# MPU-9250-mbed_rev03_FDZ.net
KiCad netlist of a schematic drawn in EAGLE
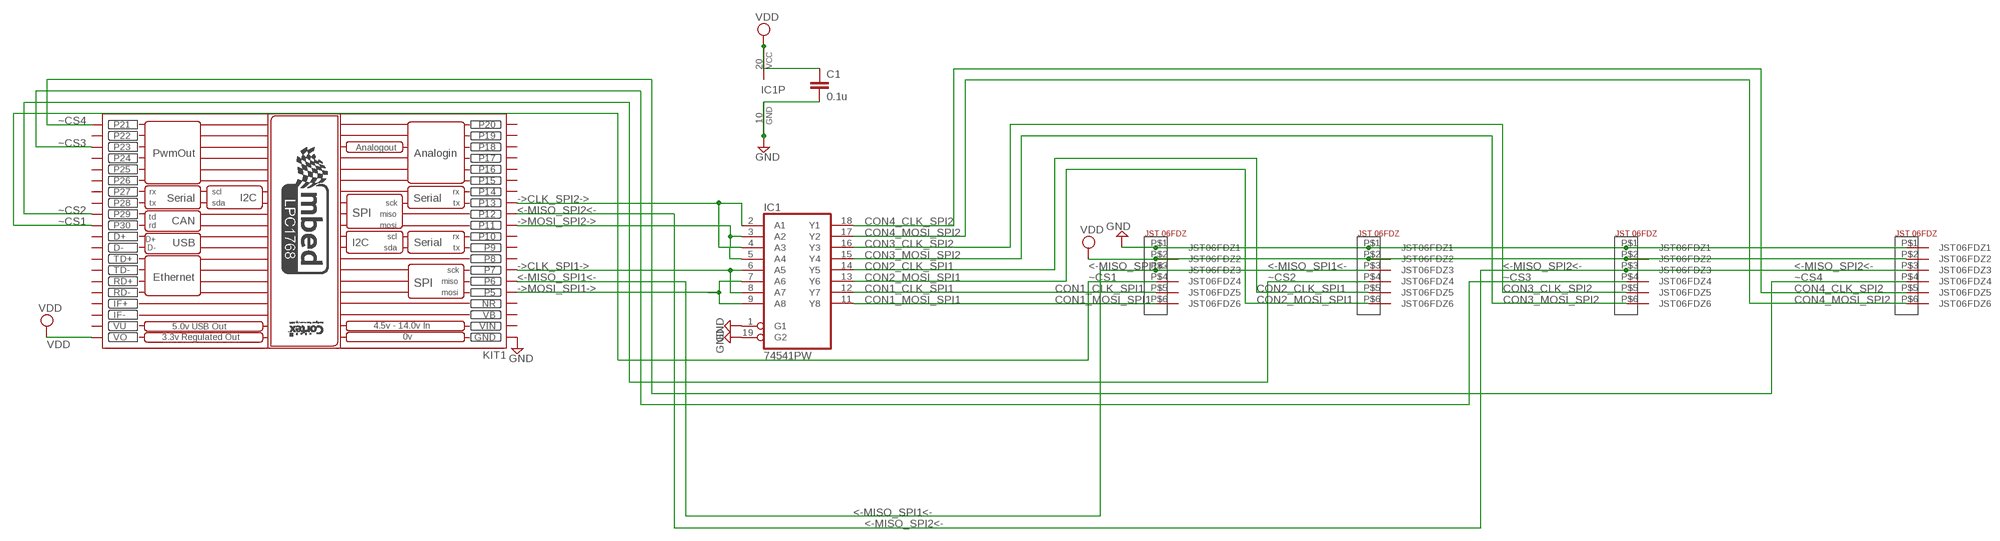
[diagram p0: schematic, sheet 1]

(export (version "E")
  (design (tool "Eeschema 10.0.6"))
  (components
    (comp (ref "C1")
      (value "0.1u")
      (footprint "eagle-import:C5B3")
      (libsource (lib "eagle-import") (part "C5/3"))
    )
    (comp (ref "CH0")
      (value "CH0")
      (footprint "eagle-import:06FDZ-ST(S)")
      (libsource (lib "eagle-import") (part "06FDZ-ST(S)"))
    )
    (comp (ref "IC1")
      (value "74541PW")
      (footprint "eagle-import:TSSOP20")
      (libsource (lib "eagle-import") (part "74541PW"))
    )
    (comp (ref "KIT1")
      (value "MBED_NXP_LPC1768")
      (footprint "eagle-import:MBED-KIT")
      (libsource (lib "eagle-import") (part "MBED_NXP_LPC1768"))
    )
    (comp (ref "U$2")
      (value "06FDZ-ST(S)")
      (footprint "eagle-import:06FDZ-ST(S)")
      (libsource (lib "eagle-import") (part "06FDZ-ST(S)"))
    )
    (comp (ref "U$3")
      (value "06FDZ-ST(S)")
      (footprint "eagle-import:06FDZ-ST(S)")
      (libsource (lib "eagle-import") (part "06FDZ-ST(S)"))
    )
    (comp (ref "U$4")
      (value "06FDZ-ST(S)")
      (footprint "eagle-import:06FDZ-ST(S)")
      (libsource (lib "eagle-import") (part "06FDZ-ST(S)"))
    )
  )
  (nets
    (net (code "1") (name "/->CLK_SPI1->") (class "Default")
      (node (ref "IC1") (pin "6") (pinfunction "A5_6") (pintype "input"))
      (node (ref "IC1") (pin "8") (pinfunction "A7_8") (pintype "input"))
      (node (ref "KIT1") (pin "P$7") (pinfunction "P7_P$7") (pintype "bidirectional"))
    )
    (net (code "2") (name "/->CLK_SPI2->") (class "Default")
      (node (ref "IC1") (pin "2") (pinfunction "A1_2") (pintype "input"))
      (node (ref "IC1") (pin "4") (pinfunction "A3_4") (pintype "input"))
      (node (ref "KIT1") (pin "P$13") (pinfunction "P13_P$13") (pintype "bidirectional"))
    )
    (net (code "3") (name "/->MOSI_SPI1->") (class "Default")
      (node (ref "IC1") (pin "7") (pinfunction "A6_7") (pintype "input"))
      (node (ref "IC1") (pin "9") (pinfunction "A8_9") (pintype "input"))
      (node (ref "KIT1") (pin "P$5") (pinfunction "P5_P$5") (pintype "bidirectional"))
    )
    (net (code "4") (name "/->MOSI_SPI2->") (class "Default")
      (node (ref "IC1") (pin "3") (pinfunction "A2_3") (pintype "input"))
      (node (ref "IC1") (pin "5") (pinfunction "A4_5") (pintype "input"))
      (node (ref "KIT1") (pin "P$11") (pinfunction "P11_P$11") (pintype "bidirectional"))
    )
    (net (code "5") (name "/<-MISO_SPI1<-") (class "Default")
      (node (ref "CH0") (pin "P$3") (pinfunction "JST06FDZ3_P$3") (pintype "bidirectional"))
      (node (ref "KIT1") (pin "P$6") (pinfunction "P6_P$6") (pintype "bidirectional"))
      (node (ref "U$2") (pin "P$3") (pinfunction "JST06FDZ3_P$3") (pintype "bidirectional"))
    )
    (net (code "6") (name "/<-MISO_SPI2<-") (class "Default")
      (node (ref "KIT1") (pin "P$12") (pinfunction "P12_P$12") (pintype "bidirectional"))
      (node (ref "U$3") (pin "P$3") (pinfunction "JST06FDZ3_P$3") (pintype "bidirectional"))
      (node (ref "U$4") (pin "P$3") (pinfunction "JST06FDZ3_P$3") (pintype "bidirectional"))
    )
    (net (code "7") (name "/CON1_CLK_SPI1") (class "Default")
      (node (ref "CH0") (pin "P$5") (pinfunction "JST06FDZ5_P$5") (pintype "bidirectional"))
      (node (ref "IC1") (pin "12") (pinfunction "Y7_12") (pintype "tri_state"))
    )
    (net (code "8") (name "/CON1_MOSI_SPI1") (class "Default")
      (node (ref "CH0") (pin "P$6") (pinfunction "JST06FDZ6_P$6") (pintype "bidirectional"))
      (node (ref "IC1") (pin "11") (pinfunction "Y8_11") (pintype "tri_state"))
    )
    (net (code "9") (name "/CON2_CLK_SPI1") (class "Default")
      (node (ref "IC1") (pin "14") (pinfunction "Y5_14") (pintype "tri_state"))
      (node (ref "U$2") (pin "P$5") (pinfunction "JST06FDZ5_P$5") (pintype "bidirectional"))
    )
    (net (code "10") (name "/CON2_MOSI_SPI1") (class "Default")
      (node (ref "IC1") (pin "13") (pinfunction "Y6_13") (pintype "tri_state"))
      (node (ref "U$2") (pin "P$6") (pinfunction "JST06FDZ6_P$6") (pintype "bidirectional"))
    )
    (net (code "11") (name "/CON3_CLK_SPI2") (class "Default")
      (node (ref "IC1") (pin "16") (pinfunction "Y3_16") (pintype "tri_state"))
      (node (ref "U$3") (pin "P$5") (pinfunction "JST06FDZ5_P$5") (pintype "bidirectional"))
    )
    (net (code "12") (name "/CON3_MOSI_SPI2") (class "Default")
      (node (ref "IC1") (pin "15") (pinfunction "Y4_15") (pintype "tri_state"))
      (node (ref "U$3") (pin "P$6") (pinfunction "JST06FDZ6_P$6") (pintype "bidirectional"))
    )
    (net (code "13") (name "/CON4_CLK_SPI2") (class "Default")
      (node (ref "IC1") (pin "18") (pinfunction "Y1_18") (pintype "tri_state"))
      (node (ref "U$4") (pin "P$5") (pinfunction "JST06FDZ5_P$5") (pintype "bidirectional"))
    )
    (net (code "14") (name "/CON4_MOSI_SPI2") (class "Default")
      (node (ref "IC1") (pin "17") (pinfunction "Y2_17") (pintype "tri_state"))
      (node (ref "U$4") (pin "P$6") (pinfunction "JST06FDZ6_P$6") (pintype "bidirectional"))
    )
    (net (code "15") (name "/NR") (class "Default")
      (node (ref "KIT1") (pin "NR") (pinfunction "NR_NR") (pintype "power_in"))
    )
    (net (code "16") (name "/VB") (class "Default")
      (node (ref "KIT1") (pin "VB") (pinfunction "VB_VB") (pintype "power_in"))
    )
    (net (code "17") (name "/VIN") (class "Default")
      (node (ref "KIT1") (pin "VIN") (pinfunction "VIN_VIN") (pintype "power_in"))
    )
    (net (code "18") (name "/VU") (class "Default")
      (node (ref "KIT1") (pin "VU") (pinfunction "VU_VU") (pintype "power_in"))
    )
    (net (code "19") (name "/~{CS1}") (class "Default")
      (node (ref "CH0") (pin "P$4") (pinfunction "JST06FDZ4_P$4") (pintype "bidirectional"))
      (node (ref "KIT1") (pin "P$30") (pinfunction "P30_P$30") (pintype "bidirectional"))
    )
    (net (code "20") (name "/~{CS2}") (class "Default")
      (node (ref "KIT1") (pin "P$29") (pinfunction "P29_P$29") (pintype "bidirectional"))
      (node (ref "U$2") (pin "P$4") (pinfunction "JST06FDZ4_P$4") (pintype "bidirectional"))
    )
    (net (code "21") (name "/~{CS3}") (class "Default")
      (node (ref "KIT1") (pin "P$23") (pinfunction "P23_P$23") (pintype "bidirectional"))
      (node (ref "U$3") (pin "P$4") (pinfunction "JST06FDZ4_P$4") (pintype "bidirectional"))
    )
    (net (code "22") (name "/~{CS4}") (class "Default")
      (node (ref "KIT1") (pin "P$21") (pinfunction "P21_P$21") (pintype "bidirectional"))
      (node (ref "U$4") (pin "P$4") (pinfunction "JST06FDZ4_P$4") (pintype "bidirectional"))
    )
    (net (code "23") (name "GND") (class "Default")
      (node (ref "C1") (pin "2") (pinfunction "2_2") (pintype "passive"))
      (node (ref "CH0") (pin "P$1") (pinfunction "JST06FDZ1_P$1") (pintype "bidirectional"))
      (node (ref "IC1") (pin "1") (pinfunction "G1_1") (pintype "input"))
      (node (ref "IC1") (pin "10") (pinfunction "GND_10") (pintype "power_in"))
      (node (ref "IC1") (pin "19") (pinfunction "G2_19") (pintype "input"))
      (node (ref "KIT1") (pin "GND") (pinfunction "GND_GND") (pintype "power_in"))
      (node (ref "U$2") (pin "P$1") (pinfunction "JST06FDZ1_P$1") (pintype "bidirectional"))
      (node (ref "U$3") (pin "P$1") (pinfunction "JST06FDZ1_P$1") (pintype "bidirectional"))
      (node (ref "U$4") (pin "P$1") (pinfunction "JST06FDZ1_P$1") (pintype "bidirectional"))
    )
    (net (code "24") (name "VDD") (class "Default")
      (node (ref "C1") (pin "1") (pinfunction "1_1") (pintype "passive"))
      (node (ref "CH0") (pin "P$2") (pinfunction "JST06FDZ2_P$2") (pintype "bidirectional"))
      (node (ref "IC1") (pin "20") (pinfunction "VCC_20") (pintype "power_in"))
      (node (ref "KIT1") (pin "VOUT") (pinfunction "VO_VOUT") (pintype "power_in"))
      (node (ref "U$2") (pin "P$2") (pinfunction "JST06FDZ2_P$2") (pintype "bidirectional"))
      (node (ref "U$3") (pin "P$2") (pinfunction "JST06FDZ2_P$2") (pintype "bidirectional"))
      (node (ref "U$4") (pin "P$2") (pinfunction "JST06FDZ2_P$2") (pintype "bidirectional"))
    )
    (net (code "25") (name "unconnected-(KIT1-P8-PadP$8)") (class "Default")
      (node (ref "KIT1") (pin "P$8") (pinfunction "P8_P$8") (pintype "bidirectional"))
    )
    (net (code "26") (name "unconnected-(KIT1-P9-PadP$9)") (class "Default")
      (node (ref "KIT1") (pin "P$9") (pinfunction "P9_P$9") (pintype "bidirectional"))
    )
    (net (code "27") (name "unconnected-(KIT1-P10-PadP$10)") (class "Default")
      (node (ref "KIT1") (pin "P$10") (pinfunction "P10_P$10") (pintype "bidirectional"))
    )
    (net (code "28") (name "unconnected-(KIT1-P14-PadP$14)") (class "Default")
      (node (ref "KIT1") (pin "P$14") (pinfunction "P14_P$14") (pintype "bidirectional"))
    )
    (net (code "29") (name "unconnected-(KIT1-P15-PadP$15)") (class "Default")
      (node (ref "KIT1") (pin "P$15") (pinfunction "P15_P$15") (pintype "bidirectional"))
    )
    (net (code "30") (name "unconnected-(KIT1-P16-PadP$16)") (class "Default")
      (node (ref "KIT1") (pin "P$16") (pinfunction "P16_P$16") (pintype "bidirectional"))
    )
    (net (code "31") (name "unconnected-(KIT1-P17-PadP$17)") (class "Default")
      (node (ref "KIT1") (pin "P$17") (pinfunction "P17_P$17") (pintype "bidirectional"))
    )
    (net (code "32") (name "unconnected-(KIT1-P18-PadP$18)") (class "Default")
      (node (ref "KIT1") (pin "P$18") (pinfunction "P18_P$18") (pintype "bidirectional"))
    )
    (net (code "33") (name "unconnected-(KIT1-P19-PadP$19)") (class "Default")
      (node (ref "KIT1") (pin "P$19") (pinfunction "P19_P$19") (pintype "bidirectional"))
    )
    (net (code "34") (name "unconnected-(KIT1-P20-PadP$20)") (class "Default")
      (node (ref "KIT1") (pin "P$20") (pinfunction "P20_P$20") (pintype "bidirectional"))
    )
    (net (code "35") (name "unconnected-(KIT1-P22-PadP$22)") (class "Default")
      (node (ref "KIT1") (pin "P$22") (pinfunction "P22_P$22") (pintype "bidirectional"))
    )
    (net (code "36") (name "unconnected-(KIT1-P24-PadP$24)") (class "Default")
      (node (ref "KIT1") (pin "P$24") (pinfunction "P24_P$24") (pintype "bidirectional"))
    )
    (net (code "37") (name "unconnected-(KIT1-P25-PadP$25)") (class "Default")
      (node (ref "KIT1") (pin "P$25") (pinfunction "P25_P$25") (pintype "bidirectional"))
    )
    (net (code "38") (name "unconnected-(KIT1-P26-PadP$26)") (class "Default")
      (node (ref "KIT1") (pin "P$26") (pinfunction "P26_P$26") (pintype "bidirectional"))
    )
    (net (code "39") (name "unconnected-(KIT1-P27-PadP$27)") (class "Default")
      (node (ref "KIT1") (pin "P$27") (pinfunction "P27_P$27") (pintype "bidirectional"))
    )
    (net (code "40") (name "unconnected-(KIT1-P28-PadP$28)") (class "Default")
      (node (ref "KIT1") (pin "P$28") (pinfunction "P28_P$28") (pintype "bidirectional"))
    )
    (net (code "41") (name "unconnected-(KIT1-PadD+)") (class "Default")
      (node (ref "KIT1") (pin "D+") (pinfunction "D+_D+") (pintype "bidirectional"))
    )
    (net (code "42") (name "unconnected-(KIT1-PadD-)") (class "Default")
      (node (ref "KIT1") (pin "D-") (pinfunction "D-_D-") (pintype "bidirectional"))
    )
    (net (code "43") (name "unconnected-(KIT1-PadIF+)") (class "Default")
      (node (ref "KIT1") (pin "IF+") (pinfunction "IF+_IF+") (pintype "bidirectional"))
    )
    (net (code "44") (name "unconnected-(KIT1-PadIF-)") (class "Default")
      (node (ref "KIT1") (pin "IF-") (pinfunction "IF-_IF-") (pintype "bidirectional"))
    )
    (net (code "45") (name "unconnected-(KIT1-PadRD+)") (class "Default")
      (node (ref "KIT1") (pin "RD+") (pinfunction "RD+_RD+") (pintype "bidirectional"))
    )
    (net (code "46") (name "unconnected-(KIT1-PadRD-)") (class "Default")
      (node (ref "KIT1") (pin "RD-") (pinfunction "RD-_RD-") (pintype "bidirectional"))
    )
    (net (code "47") (name "unconnected-(KIT1-PadTD+)") (class "Default")
      (node (ref "KIT1") (pin "TD+") (pinfunction "TD+_TD+") (pintype "bidirectional"))
    )
    (net (code "48") (name "unconnected-(KIT1-PadTD-)") (class "Default")
      (node (ref "KIT1") (pin "TD-") (pinfunction "TD-_TD-") (pintype "bidirectional"))
    )
  )
)
